# 15_LMS2_RF1_Misc.net
KiCad netlist of a schematic drawn in Altium Designer
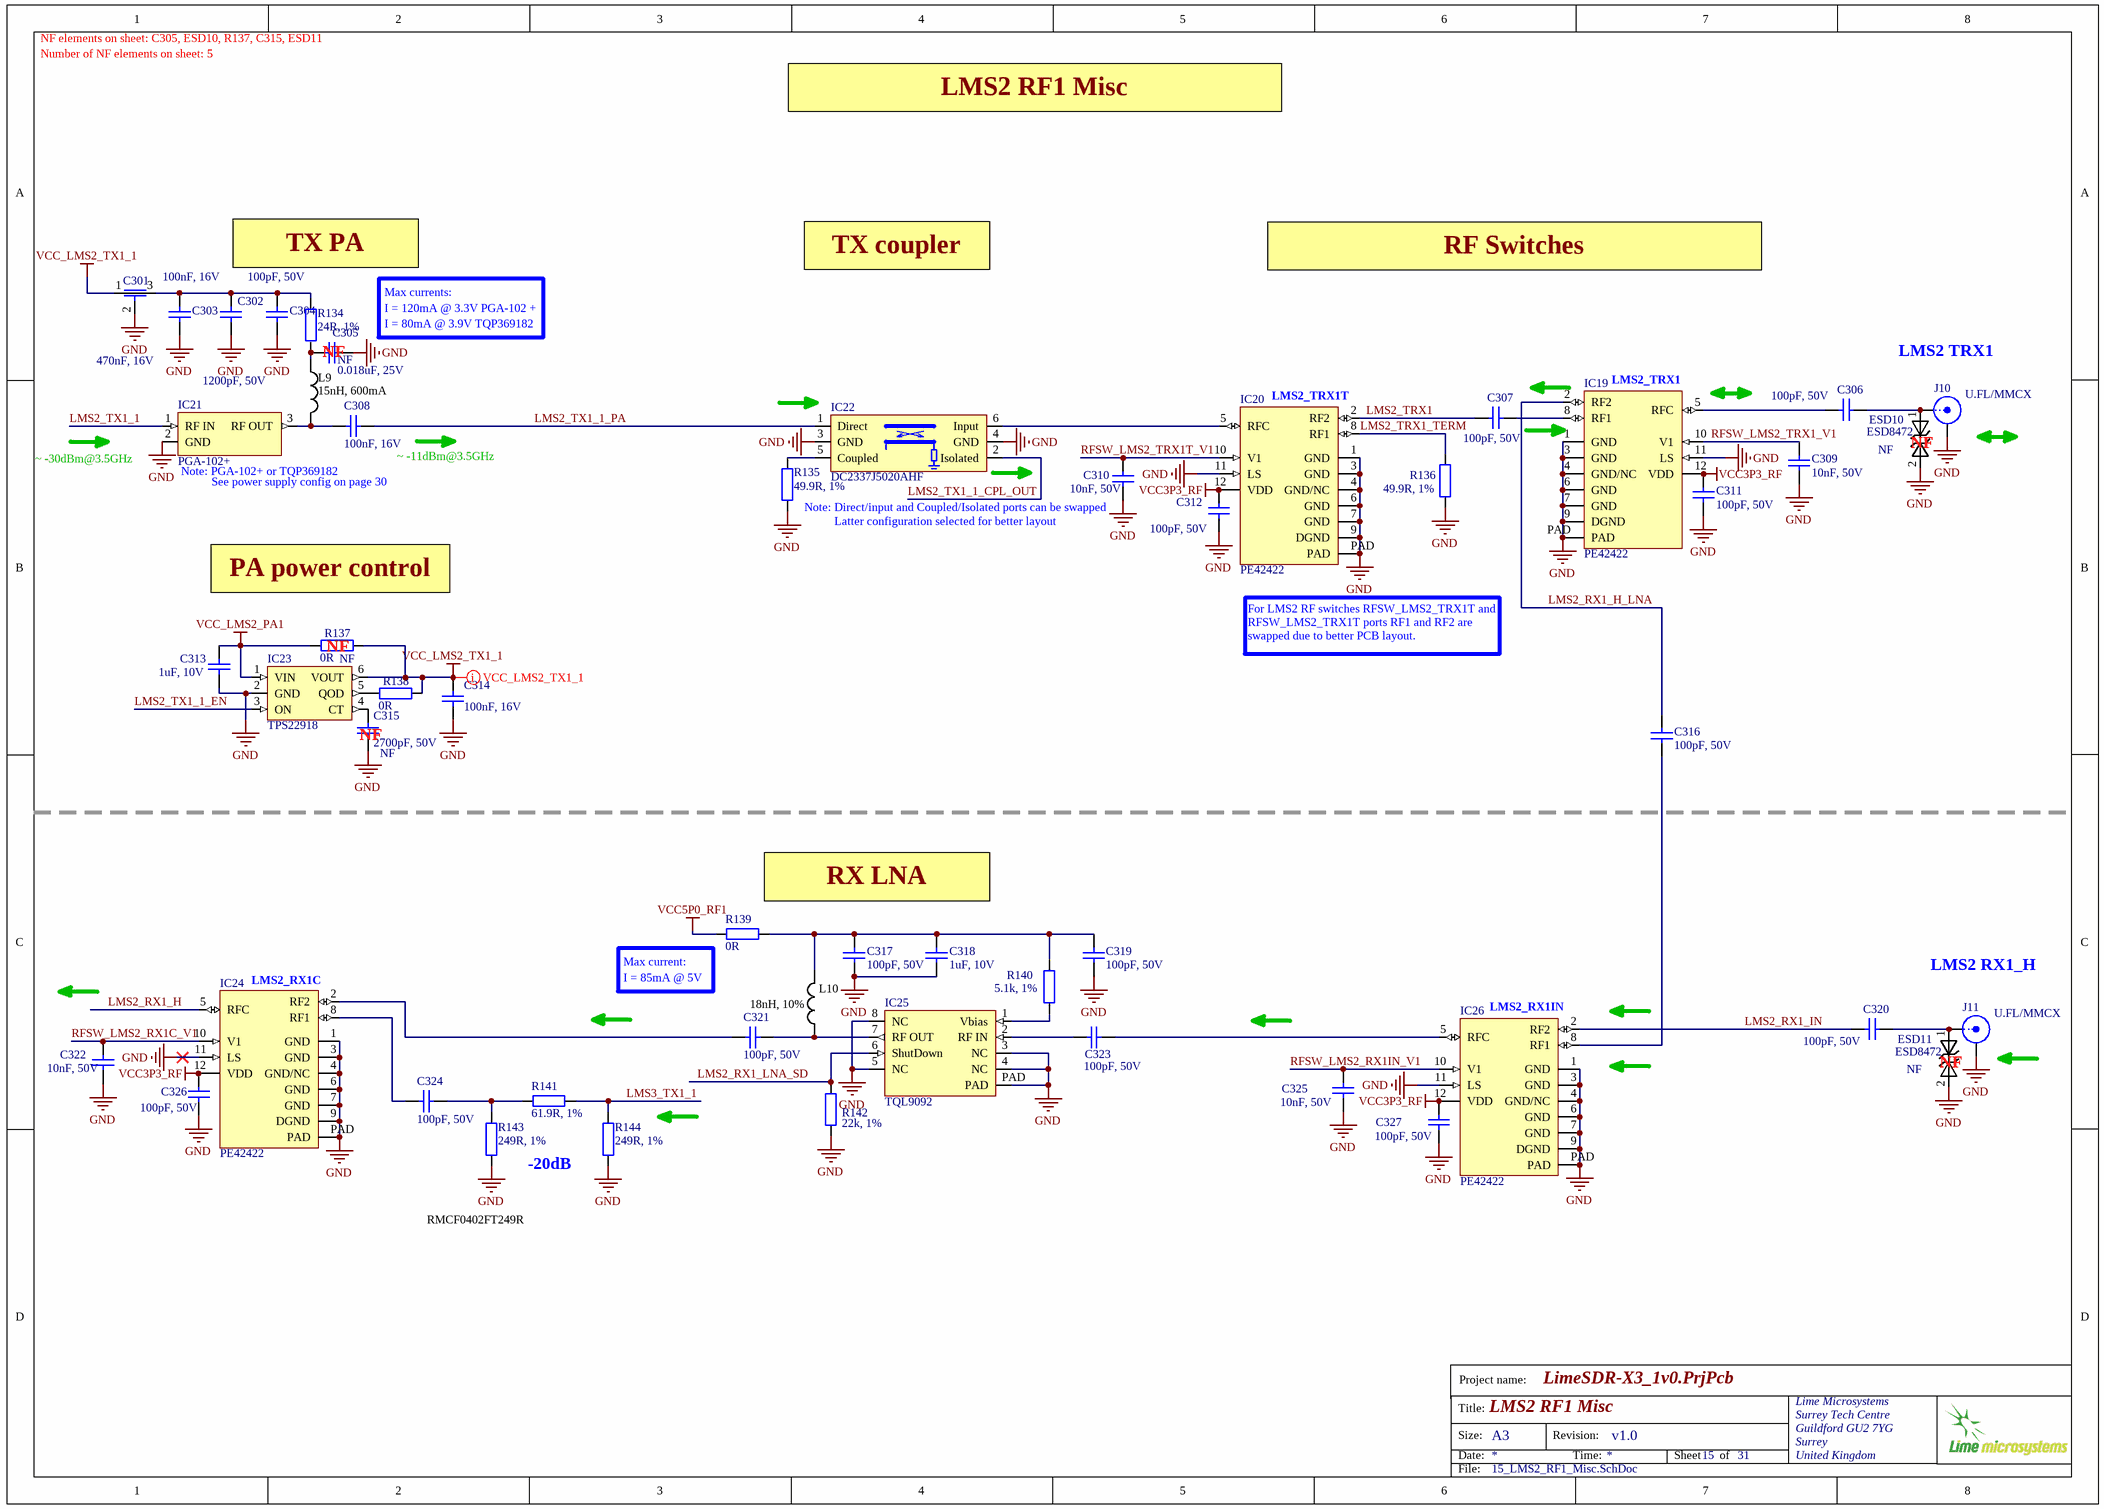
[diagram p0: 15_LMS2_RF1_Misc.SchDoc]

(export (version "E")
  (design (tool "Eeschema 10.0.6"))
  (components
    (comp (ref "C301")
      (value "470nF, 16V")
      (footprint "CAP0805_FEEDTHROUGH")
      (fields
        (field (name "MANUFACTURER") "Murata")
        (field (name "TOLERANCE") "20%")
        (field (name "VOLTAGE") "16V")
      )
      (libsource (lib "LimeMicroAltiumLib_schLib_r01") (part "Cap_feed_through"))
    )
    (comp (ref "C302")
      (value "1200pF, 50V")
      (footprint "CAP0402")
      (fields (field (name "MANUFACTURER") "Kemet") (field (name "TOLERANCE") "±5%"))
      (libsource (lib "") (part "Cap_0402_11"))
    )
    (comp (ref "C303")
      (value "100nF, 16V")
      (footprint "CAP0402")
      (fields (field (name "MANUFACTURER") "Murata Electronics") (field (name "TOLERANCE") "10 %"))
      (libsource (lib "") (part "Cap_0402_4"))
    )
    (comp (ref "C304")
      (value "100pF, 50V")
      (footprint "CAP0402")
      (fields (field (name "TOLERANCE") "±5%") (field (name "MANUFACTURER") "Yageo"))
      (libsource (lib "") (part "Cap_0402_4"))
    )
    (comp (ref "C305")
      (value "0.018uF, 25V")
      (footprint "CAP0402")
      (fields
        (field (name "ASSEMBLY INFO") "NF")
        (field (name "MANUFACTURER") "Yageo")
        (field (name "TOLERANCE") "10%")
      )
      (libsource (lib "") (part "Cap_0402_2"))
    )
    (comp (ref "C306")
      (value "100pF, 50V")
      (footprint "CAP0402")
      (fields (field (name "TOLERANCE") "±5%") (field (name "MANUFACTURER") "Yageo"))
      (libsource (lib "") (part "Cap_0402_1"))
    )
    (comp (ref "C307")
      (value "100pF, 50V")
      (footprint "CAP0402")
      (fields (field (name "TOLERANCE") "±5%") (field (name "MANUFACTURER") "Yageo"))
      (libsource (lib "") (part "Cap_0402_1"))
    )
    (comp (ref "C308")
      (value "100nF, 16V")
      (footprint "CAP0402")
      (fields (field (name "MANUFACTURER") "Murata Electronics") (field (name "TOLERANCE") "10 %"))
      (libsource (lib "") (part "Cap_0402_5"))
    )
    (comp (ref "C309")
      (value "10nF, 50V")
      (footprint "CAP0402")
      (fields
        (field (name "MANUFACTURER") "Murata Electronics North America")
        (field (name "TOLERANCE") "±10%")
      )
      (libsource (lib "") (part "Cap_0402_10"))
    )
    (comp (ref "C310")
      (value "10nF, 50V")
      (footprint "CAP0402")
      (fields
        (field (name "MANUFACTURER") "Murata Electronics North America")
        (field (name "TOLERANCE") "±10%")
      )
      (libsource (lib "") (part "Cap_0402_10"))
    )
    (comp (ref "C311")
      (value "100pF, 50V")
      (footprint "CAP0402")
      (fields (field (name "TOLERANCE") "±5%") (field (name "MANUFACTURER") "Yageo"))
      (libsource (lib "") (part "Cap_0402_6"))
    )
    (comp (ref "C312")
      (value "100pF, 50V")
      (footprint "CAP0402")
      (fields (field (name "TOLERANCE") "±5%") (field (name "MANUFACTURER") "Yageo"))
      (libsource (lib "") (part "Cap_0402_6"))
    )
    (comp (ref "C313")
      (value "1uF, 10V")
      (footprint "CAP0402")
      (fields (field (name "MANUFACTURER") "TDK"))
      (libsource (lib "LimeMicroAltiumLib_schLib") (part "Cap_0402"))
    )
    (comp (ref "C314")
      (value "100nF, 16V")
      (footprint "CAP0402")
      (fields (field (name "MANUFACTURER") "Murata Electronics") (field (name "TOLERANCE") "10 %"))
      (libsource (lib "LimeMicroAltiumLib_schLib") (part "Cap_0402"))
    )
    (comp (ref "C315")
      (value "2700pF, 50V")
      (footprint "CAP0402")
      (fields
        (field (name "ASSEMBLY INFO") "NF")
        (field (name "TOLERANCE") "±10%")
        (field (name "MANUFACTURER") "Murata Electronics North America")
      )
      (libsource (lib "") (part "Cap_0402_4"))
    )
    (comp (ref "C316")
      (value "100pF, 50V")
      (footprint "CAP0402")
      (fields (field (name "TOLERANCE") "±5%") (field (name "MANUFACTURER") "Yageo"))
      (libsource (lib "") (part "Cap_0402_1"))
    )
    (comp (ref "C317")
      (value "100pF, 50V")
      (footprint "CAP0402")
      (fields (field (name "TOLERANCE") "±5%") (field (name "MANUFACTURER") "Yageo"))
      (libsource (lib "") (part "Cap_0402_3"))
    )
    (comp (ref "C318")
      (value "1uF, 10V")
      (footprint "CAP0402")
      (fields (field (name "MANUFACTURER") "TDK"))
      (libsource (lib "") (part "Cap_0402_8"))
    )
    (comp (ref "C319")
      (value "100pF, 50V")
      (footprint "CAP0402")
      (fields (field (name "TOLERANCE") "±5%") (field (name "MANUFACTURER") "Yageo"))
      (libsource (lib "") (part "Cap_0402_3"))
    )
    (comp (ref "C320")
      (value "100pF, 50V")
      (footprint "CAP0402")
      (fields (field (name "TOLERANCE") "±5%") (field (name "MANUFACTURER") "Yageo"))
      (libsource (lib "") (part "Cap_0402_1"))
    )
    (comp (ref "C321")
      (value "100pF, 50V")
      (footprint "CAP0402")
      (fields (field (name "TOLERANCE") "±5%") (field (name "MANUFACTURER") "Yageo"))
      (libsource (lib "LimeMicroAltiumLib_schLib") (part "Cap_0402"))
    )
    (comp (ref "C322")
      (value "10nF, 50V")
      (footprint "CAP0402")
      (fields
        (field (name "MANUFACTURER") "Murata Electronics North America")
        (field (name "TOLERANCE") "±10%")
      )
      (libsource (lib "") (part "Cap_0402_12"))
    )
    (comp (ref "C323")
      (value "100pF, 50V")
      (footprint "CAP0402")
      (fields (field (name "TOLERANCE") "±5%") (field (name "MANUFACTURER") "Yageo"))
      (libsource (lib "") (part "Cap_0402_7"))
    )
    (comp (ref "C324")
      (value "100pF, 50V")
      (footprint "CAP0402")
      (fields (field (name "TOLERANCE") "±5%") (field (name "MANUFACTURER") "Yageo"))
      (libsource (lib "") (part "Cap_0402_1"))
    )
    (comp (ref "C325")
      (value "10nF, 50V")
      (footprint "CAP0402")
      (fields
        (field (name "MANUFACTURER") "Murata Electronics North America")
        (field (name "TOLERANCE") "±10%")
      )
      (libsource (lib "") (part "Cap_0402_2"))
    )
    (comp (ref "C326")
      (value "100pF, 50V")
      (footprint "CAP0402")
      (fields (field (name "TOLERANCE") "±5%") (field (name "MANUFACTURER") "Yageo"))
      (libsource (lib "") (part "Cap_0402_9"))
    )
    (comp (ref "C327")
      (value "100pF, 50V")
      (footprint "CAP0402")
      (fields (field (name "TOLERANCE") "±5%") (field (name "MANUFACTURER") "Yageo"))
      (libsource (lib "") (part "Cap_0402_5"))
    )
    (comp (ref "ESD10")
      (value "ESD8472")
      (footprint "ESD8472_X3DFN2")
      (fields (field (name "MANUFACTURER") "ON Semiconductor") (field (name "ASSEMBLY INFO") "NF"))
      (libsource (lib "") (part "ESD8472_1"))
    )
    (comp (ref "ESD11")
      (value "ESD8472")
      (footprint "ESD8472_X3DFN2")
      (fields (field (name "MANUFACTURER") "ON Semiconductor") (field (name "ASSEMBLY INFO") "NF"))
      (libsource (lib "LimeMicroAltiumLib_schLib") (part "ESD8472"))
    )
    (comp (ref "IC19")
      (value "PE42422")
      (footprint "PE42422_QFN12")
      (fields (field (name "MANUFACTURER") "Peregrine Semiconductor"))
      (libsource (lib "") (part "PE42422_2"))
    )
    (comp (ref "IC20")
      (value "PE42422")
      (footprint "PE42422_QFN12")
      (fields (field (name "MANUFACTURER") "Peregrine Semiconductor"))
      (libsource (lib "LimeMicroAltiumLib_schLib") (part "PE42422"))
    )
    (comp (ref "IC21")
      (value "PGA-102+")
      (footprint "PGA-102+_SOT89")
      (fields (field (name "MANUFACTURER") "Qorvo"))
      (libsource (lib "LimeMicroAltiumLib_schLib_r01") (part "PGA-102+_PA"))
    )
    (comp (ref "IC22")
      (value "DC2337J5020AHF")
      (footprint "DC2337J5020AHF_ANAREN_COUPLER_0805")
      (fields (field (name "MANUFACTURER") "Anaren"))
      (libsource (lib "LimeMicroAltiumLib_schLib_r02") (part "DC2337J5020AHF_coupler"))
    )
    (comp (ref "IC23")
      (value "TPS22918")
      (footprint "SOT23-6")
      (fields (field (name "MANUFACTURER") "Texas Instruments"))
      (libsource (lib "LimeMicroAltiumLib_schLib") (part "TPS22918"))
    )
    (comp (ref "IC24")
      (value "PE42422")
      (footprint "PE42422_QFN12")
      (fields (field (name "MANUFACTURER") "Peregrine Semiconductor"))
      (libsource (lib "") (part "PE42422_3"))
    )
    (comp (ref "IC25")
      (value "TQL9092")
      (footprint "TQL9092")
      (fields (field (name "MANUFACTURER") "Qorvo"))
      (libsource (lib "LimeMicroAltiumLib_schLib") (part "TQL9092"))
    )
    (comp (ref "IC26")
      (value "PE42422")
      (footprint "PE42422_QFN12")
      (fields (field (name "MANUFACTURER") "Peregrine Semiconductor"))
      (libsource (lib "") (part "PE42422_1"))
    )
    (comp (ref "J10")
      (value "U.FL/MMCX")
      (footprint "MMCX_UFL_conn_m")
      (description "CONN UMC RCPT STR 50 OHM SMD")
      (fields (field (name "MANUFACTURER") "Amphenol RF"))
      (libsource (lib "LimeMicroAltiumLib_schLib") (part "RF_IF_connector"))
    )
    (comp (ref "J11")
      (value "U.FL/MMCX")
      (footprint "MMCX_UFL_conn_m")
      (description "CONN UMC RCPT STR 50 OHM SMD")
      (fields (field (name "MANUFACTURER") "Amphenol RF"))
      (libsource (lib "LimeMicroAltiumLib_schLib") (part "RF_IF_connector"))
    )
    (comp (ref "L9")
      (value "15nH, 600mA")
      (footprint "RES0805")
      (fields (field (name "MANUFACTURER") "Bourns") (field (name "TOLERANCE") "5%"))
      (libsource (lib "LimeMicroAltiumLib_schLib") (part "Inductor_0603"))
    )
    (comp (ref "L10")
      (value "18nH, 10%")
      (footprint "RES0603")
      (fields (field (name "MANUFACTURER") "Pulse Electronics Network") (field (name "TOLERANCE") "±10%"))
      (libsource (lib "LimeMicroAltiumLib_schLib") (part "Inductor"))
    )
    (comp (ref "R134")
      (value "24R, 1%")
      (footprint "RES0402")
      (fields (field (name "MANUFACTURER") "Yageo") (field (name "TOLERANCE") "1%"))
      (libsource (lib "LimeFPGAboard_schLib") (part "Res_0402"))
    )
    (comp (ref "R135")
      (value "49.9R, 1%")
      (footprint "RES0402")
      (fields
        (field (name "TOLERANCE") "±1%")
        (field (name "MANUFACTURER") "Samsung Electro-Mechanics America, Inc.")
        (field (name "MANUFACTURER PART NUMBER") "RC1005F49R9CS")
      )
      (libsource (lib "LimeMicroAltiumLib_schLib") (part "Res_0402"))
    )
    (comp (ref "R136")
      (value "49.9R, 1%")
      (footprint "RES0402")
      (fields
        (field (name "TOLERANCE") "±1%")
        (field (name "MANUFACTURER") "Samsung Electro-Mechanics America, Inc.")
        (field (name "MANUFACTURER PART NUMBER") "RC1005F49R9CS")
      )
      (libsource (lib "LimeMicroAltiumLib_schLib") (part "Res_0402"))
    )
    (comp (ref "R137")
      (value "0R")
      (footprint "RES0402")
      (fields
        (field (name "ASSEMBLY INFO") "NF")
        (field (name "MANUFACTURER") "Yageo")
        (field (name "TOLERANCE") "Jumper")
      )
      (libsource (lib "") (part "Res_0402_1"))
    )
    (comp (ref "R138")
      (value "0R")
      (footprint "RES0402")
      (fields (field (name "MANUFACTURER") "Yageo") (field (name "TOLERANCE") "Jumper"))
      (libsource (lib "") (part "Res_0402_1"))
    )
    (comp (ref "R139")
      (value "0R")
      (footprint "RES0402")
      (fields (field (name "MANUFACTURER") "Yageo") (field (name "TOLERANCE") "Jumper"))
      (libsource (lib "LimeMicroAltiumLib_schLib") (part "Res_0402"))
    )
    (comp (ref "R140")
      (value "5.1k, 1%")
      (footprint "RES0603")
      (fields (field (name "MANUFACTURER") "Stackpole Electronics") (field (name "TOLERANCE") "1%"))
      (libsource (lib "LimeMicroAltiumLib_schLib") (part "Res_0603"))
    )
    (comp (ref "R141")
      (value "61.9R, 1%")
      (footprint "RES0402")
      (fields (field (name "MANUFACTURER") "Yageo") (field (name "TOLERANCE") "1%"))
      (libsource (lib "") (part "Res_0402_1"))
    )
    (comp (ref "R142")
      (value "22k, 1%")
      (footprint "RES0402")
      (fields (field (name "MANUFACTURER") "Yageo") (field (name "TOLERANCE") "±1%"))
      (libsource (lib "") (part "Res_0402_1"))
    )
    (comp (ref "R143")
      (value "249R, 1%")
      (footprint "RES0402")
      (fields (field (name "MANUFACTURER") "Stackpole Electronics Inc") (field (name "TOLERANCE") "±1%"))
      (libsource (lib "") (part "Res_0402_1"))
    )
    (comp (ref "R144")
      (value "249R, 1%")
      (footprint "RES0402")
      (fields (field (name "MANUFACTURER") "Stackpole Electronics Inc") (field (name "TOLERANCE") "±1%"))
      (libsource (lib "") (part "Res_0402_1"))
    )
  )
  (nets
    (net (code "1") (name "/LMS2_RX1_H") (class "Default")
      (node (ref "IC24") (pin "5") (pinfunction "RFC_5") (pintype "bidirectional"))
    )
    (net (code "2") (name "/LMS2_RX1_H_LNA") (class "Default")
      (node (ref "C316") (pin "2") (pinfunction "2_2") (pintype "passive"))
      (node (ref "IC19") (pin "2") (pinfunction "RF2_2") (pintype "bidirectional"))
    )
    (net (code "3") (name "/LMS2_RX1_IN") (class "Default")
      (node (ref "C320") (pin "1") (pinfunction "1_1") (pintype "passive"))
      (node (ref "IC26") (pin "2") (pinfunction "RF2_2") (pintype "bidirectional"))
    )
    (net (code "4") (name "/LMS2_RX1_LNA_SD") (class "Default")
      (node (ref "IC25") (pin "6") (pinfunction "ShutDown_6") (pintype "input"))
      (node (ref "R142") (pin "2") (pinfunction "2_2") (pintype "passive"))
    )
    (net (code "5") (name "/LMS2_TRX1") (class "Default")
      (node (ref "C307") (pin "1") (pinfunction "1_1") (pintype "passive"))
      (node (ref "IC20") (pin "2") (pinfunction "RF2_2") (pintype "bidirectional"))
    )
    (net (code "6") (name "/LMS2_TRX1_TERM") (class "Default")
      (node (ref "IC20") (pin "8") (pinfunction "RF1_8") (pintype "bidirectional"))
      (node (ref "R136") (pin "1") (pinfunction "1_1") (pintype "passive"))
    )
    (net (code "7") (name "/LMS2_TX1_1") (class "Default")
      (node (ref "IC21") (pin "1") (pinfunction "RF_IN_1") (pintype "input"))
    )
    (net (code "8") (name "/LMS2_TX1_1_CPL_OUT") (class "Default")
      (node (ref "IC22") (pin "2") (pinfunction "Isolated_2") (pintype "passive"))
    )
    (net (code "9") (name "/LMS2_TX1_1_EN") (class "Default")
      (node (ref "IC23") (pin "3") (pinfunction "ON_3") (pintype "input"))
    )
    (net (code "10") (name "/LMS2_TX1_1_PA") (class "Default")
      (node (ref "C308") (pin "1") (pinfunction "1_1") (pintype "passive"))
      (node (ref "IC22") (pin "1") (pinfunction "Direct_1") (pintype "passive"))
    )
    (net (code "11") (name "/LMS3_TX1_1") (class "Default")
      (node (ref "R141") (pin "2") (pinfunction "2_2") (pintype "passive"))
      (node (ref "R144") (pin "2") (pinfunction "2_2") (pintype "passive"))
    )
    (net (code "12") (name "/RFSW_LMS2_RX1C_V1") (class "Default")
      (node (ref "C322") (pin "1") (pinfunction "1_1") (pintype "passive"))
      (node (ref "IC24") (pin "10") (pinfunction "V1_10") (pintype "input"))
    )
    (net (code "13") (name "/RFSW_LMS2_RX1IN_V1") (class "Default")
      (node (ref "C325") (pin "1") (pinfunction "1_1") (pintype "passive"))
      (node (ref "IC26") (pin "10") (pinfunction "V1_10") (pintype "input"))
    )
    (net (code "14") (name "/RFSW_LMS2_TRX1T_V1") (class "Default")
      (node (ref "C310") (pin "1") (pinfunction "1_1") (pintype "passive"))
      (node (ref "IC20") (pin "10") (pinfunction "V1_10") (pintype "input"))
    )
    (net (code "15") (name "/RFSW_LMS2_TRX1_V1") (class "Default")
      (node (ref "C309") (pin "1") (pinfunction "1_1") (pintype "passive"))
      (node (ref "IC19") (pin "10") (pinfunction "V1_10") (pintype "input"))
    )
    (net (code "16") (name "GND") (class "Default")
      (node (ref "C301") (pin "2") (pinfunction "2_2") (pintype "passive"))
      (node (ref "C302") (pin "2") (pinfunction "2_2") (pintype "passive"))
      (node (ref "C303") (pin "1") (pinfunction "1_1") (pintype "passive"))
      (node (ref "C304") (pin "2") (pinfunction "2_2") (pintype "passive"))
      (node (ref "C305") (pin "2") (pinfunction "2_2") (pintype "passive"))
      (node (ref "C309") (pin "2") (pinfunction "2_2") (pintype "passive"))
      (node (ref "C310") (pin "2") (pinfunction "2_2") (pintype "passive"))
      (node (ref "C311") (pin "1") (pinfunction "1_1") (pintype "passive"))
      (node (ref "C312") (pin "1") (pinfunction "1_1") (pintype "passive"))
      (node (ref "C313") (pin "1") (pinfunction "1_1") (pintype "passive"))
      (node (ref "C314") (pin "1") (pinfunction "1_1") (pintype "passive"))
      (node (ref "C315") (pin "2") (pinfunction "2_2") (pintype "passive"))
      (node (ref "C317") (pin "2") (pinfunction "2_2") (pintype "passive"))
      (node (ref "C318") (pin "1") (pinfunction "1_1") (pintype "passive"))
      (node (ref "C319") (pin "2") (pinfunction "2_2") (pintype "passive"))
      (node (ref "C322") (pin "2") (pinfunction "2_2") (pintype "passive"))
      (node (ref "C325") (pin "2") (pinfunction "2_2") (pintype "passive"))
      (node (ref "C326") (pin "1") (pinfunction "1_1") (pintype "passive"))
      (node (ref "C327") (pin "1") (pinfunction "1_1") (pintype "passive"))
      (node (ref "ESD10") (pin "2") (pinfunction "2_2") (pintype "passive"))
      (node (ref "ESD11") (pin "2") (pinfunction "2_2") (pintype "passive"))
      (node (ref "IC19") (pin "1") (pinfunction "GND_1") (pintype "passive"))
      (node (ref "IC19") (pin "11") (pinfunction "LS_11") (pintype "input"))
      (node (ref "IC19") (pin "3") (pinfunction "GND_3") (pintype "passive"))
      (node (ref "IC19") (pin "4") (pinfunction "GND/NC_4") (pintype "passive"))
      (node (ref "IC19") (pin "6") (pinfunction "GND_6") (pintype "passive"))
      (node (ref "IC19") (pin "7") (pinfunction "GND_7") (pintype "passive"))
      (node (ref "IC19") (pin "9") (pinfunction "DGND_9") (pintype "passive"))
      (node (ref "IC19") (pin "PAD") (pinfunction "PAD_PAD") (pintype "passive"))
      (node (ref "IC20") (pin "1") (pinfunction "GND_1") (pintype "passive"))
      (node (ref "IC20") (pin "11") (pinfunction "LS_11") (pintype "input"))
      (node (ref "IC20") (pin "3") (pinfunction "GND_3") (pintype "passive"))
      (node (ref "IC20") (pin "4") (pinfunction "GND/NC_4") (pintype "passive"))
      (node (ref "IC20") (pin "6") (pinfunction "GND_6") (pintype "passive"))
      (node (ref "IC20") (pin "7") (pinfunction "GND_7") (pintype "passive"))
      (node (ref "IC20") (pin "9") (pinfunction "DGND_9") (pintype "passive"))
      (node (ref "IC20") (pin "PAD") (pinfunction "PAD_PAD") (pintype "passive"))
      (node (ref "IC21") (pin "2") (pinfunction "GND_2") (pintype "passive"))
      (node (ref "IC22") (pin "3") (pinfunction "GND_3") (pintype "passive"))
      (node (ref "IC22") (pin "4") (pinfunction "GND_4") (pintype "passive"))
      (node (ref "IC23") (pin "2") (pinfunction "GND_2") (pintype "passive"))
      (node (ref "IC24") (pin "1") (pinfunction "GND_1") (pintype "passive"))
      (node (ref "IC24") (pin "11") (pinfunction "LS_11") (pintype "input"))
      (node (ref "IC24") (pin "3") (pinfunction "GND_3") (pintype "passive"))
      (node (ref "IC24") (pin "4") (pinfunction "GND/NC_4") (pintype "passive"))
      (node (ref "IC24") (pin "6") (pinfunction "GND_6") (pintype "passive"))
      (node (ref "IC24") (pin "7") (pinfunction "GND_7") (pintype "passive"))
      (node (ref "IC24") (pin "9") (pinfunction "DGND_9") (pintype "passive"))
      (node (ref "IC24") (pin "PAD") (pinfunction "PAD_PAD") (pintype "passive"))
      (node (ref "IC25") (pin "3") (pinfunction "NC_3") (pintype "passive"))
      (node (ref "IC25") (pin "4") (pinfunction "NC_4") (pintype "passive"))
      (node (ref "IC25") (pin "5") (pinfunction "NC_5") (pintype "passive"))
      (node (ref "IC25") (pin "8") (pinfunction "NC_8") (pintype "passive"))
      (node (ref "IC25") (pin "PAD") (pinfunction "PAD_PAD") (pintype "passive"))
      (node (ref "IC26") (pin "1") (pinfunction "GND_1") (pintype "passive"))
      (node (ref "IC26") (pin "11") (pinfunction "LS_11") (pintype "input"))
      (node (ref "IC26") (pin "3") (pinfunction "GND_3") (pintype "passive"))
      (node (ref "IC26") (pin "4") (pinfunction "GND/NC_4") (pintype "passive"))
      (node (ref "IC26") (pin "6") (pinfunction "GND_6") (pintype "passive"))
      (node (ref "IC26") (pin "7") (pinfunction "GND_7") (pintype "passive"))
      (node (ref "IC26") (pin "9") (pinfunction "DGND_9") (pintype "passive"))
      (node (ref "IC26") (pin "PAD") (pinfunction "PAD_PAD") (pintype "passive"))
      (node (ref "J10") (pin "2") (pinfunction "Y_2") (pintype "passive"))
      (node (ref "J11") (pin "2") (pinfunction "Y_2") (pintype "passive"))
      (node (ref "R135") (pin "2") (pinfunction "2_2") (pintype "passive"))
      (node (ref "R136") (pin "2") (pinfunction "2_2") (pintype "passive"))
      (node (ref "R142") (pin "1") (pinfunction "1_1") (pintype "passive"))
      (node (ref "R143") (pin "1") (pinfunction "1_1") (pintype "passive"))
      (node (ref "R144") (pin "1") (pinfunction "1_1") (pintype "passive"))
    )
    (net (code "17") (name "Net-(C301-Pad3)") (class "Default")
      (node (ref "C301") (pin "3") (pinfunction "3_3") (pintype "passive"))
      (node (ref "C302") (pin "1") (pinfunction "1_1") (pintype "passive"))
      (node (ref "C303") (pin "2") (pinfunction "2_2") (pintype "passive"))
      (node (ref "C304") (pin "1") (pinfunction "1_1") (pintype "passive"))
      (node (ref "R134") (pin "1") (pinfunction "1_1") (pintype "passive"))
    )
    (net (code "18") (name "Net-(C305-Pad1)") (class "Default")
      (node (ref "C305") (pin "1") (pinfunction "1_1") (pintype "passive"))
      (node (ref "L9") (pin "1") (pinfunction "1_1") (pintype "passive"))
      (node (ref "R134") (pin "2") (pinfunction "2_2") (pintype "passive"))
    )
    (net (code "19") (name "Net-(C317-Pad1)") (class "Default")
      (node (ref "C317") (pin "1") (pinfunction "1_1") (pintype "passive"))
      (node (ref "C318") (pin "2") (pinfunction "2_2") (pintype "passive"))
      (node (ref "C319") (pin "1") (pinfunction "1_1") (pintype "passive"))
      (node (ref "L10") (pin "1") (pinfunction "1_1") (pintype "passive"))
      (node (ref "R139") (pin "2") (pinfunction "2_2") (pintype "passive"))
      (node (ref "R140") (pin "2") (pinfunction "2_2") (pintype "passive"))
    )
    (net (code "20") (name "Net-(C324-Pad1)") (class "Default")
      (node (ref "C324") (pin "1") (pinfunction "1_1") (pintype "passive"))
      (node (ref "R141") (pin "1") (pinfunction "1_1") (pintype "passive"))
      (node (ref "R143") (pin "2") (pinfunction "2_2") (pintype "passive"))
    )
    (net (code "21") (name "Net-(IC19-RF1)") (class "Default")
      (node (ref "C307") (pin "2") (pinfunction "2_2") (pintype "passive"))
      (node (ref "IC19") (pin "8") (pinfunction "RF1_8") (pintype "bidirectional"))
    )
    (net (code "22") (name "Net-(IC19-RFC)") (class "Default")
      (node (ref "C306") (pin "1") (pinfunction "1_1") (pintype "passive"))
      (node (ref "IC19") (pin "5") (pinfunction "RFC_5") (pintype "bidirectional"))
    )
    (net (code "23") (name "Net-(IC20-RFC)") (class "Default")
      (node (ref "IC20") (pin "5") (pinfunction "RFC_5") (pintype "bidirectional"))
      (node (ref "IC22") (pin "6") (pinfunction "Input_6") (pintype "passive"))
    )
    (net (code "24") (name "Net-(IC21-RF_OUT)") (class "Default")
      (node (ref "C308") (pin "2") (pinfunction "2_2") (pintype "passive"))
      (node (ref "IC21") (pin "3") (pinfunction "RF_OUT_3") (pintype "output"))
      (node (ref "L9") (pin "2") (pinfunction "2_2") (pintype "passive"))
    )
    (net (code "25") (name "Net-(IC22-Coupled)") (class "Default")
      (node (ref "IC22") (pin "5") (pinfunction "Coupled_5") (pintype "passive"))
      (node (ref "R135") (pin "1") (pinfunction "1_1") (pintype "passive"))
    )
    (net (code "26") (name "Net-(IC23-CT)") (class "Default")
      (node (ref "C315") (pin "1") (pinfunction "1_1") (pintype "passive"))
      (node (ref "IC23") (pin "4") (pinfunction "CT_4") (pintype "output"))
    )
    (net (code "27") (name "Net-(IC23-QOD)") (class "Default")
      (node (ref "IC23") (pin "5") (pinfunction "QOD_5") (pintype "output"))
      (node (ref "R138") (pin "2") (pinfunction "2_2") (pintype "passive"))
    )
    (net (code "28") (name "Net-(IC24-RF1)") (class "Default")
      (node (ref "C324") (pin "2") (pinfunction "2_2") (pintype "passive"))
      (node (ref "IC24") (pin "8") (pinfunction "RF1_8") (pintype "bidirectional"))
    )
    (net (code "29") (name "Net-(IC24-RF2)") (class "Default")
      (node (ref "C321") (pin "1") (pinfunction "1_1") (pintype "passive"))
      (node (ref "IC24") (pin "2") (pinfunction "RF2_2") (pintype "bidirectional"))
    )
    (net (code "30") (name "Net-(IC25-RF_IN)") (class "Default")
      (node (ref "C323") (pin "1") (pinfunction "1_1") (pintype "passive"))
      (node (ref "IC25") (pin "2") (pinfunction "RF_IN_2") (pintype "input"))
    )
    (net (code "31") (name "Net-(IC25-RF_OUT)") (class "Default")
      (node (ref "C321") (pin "2") (pinfunction "2_2") (pintype "passive"))
      (node (ref "IC25") (pin "7") (pinfunction "RF_OUT_7") (pintype "output"))
      (node (ref "L10") (pin "2") (pinfunction "2_2") (pintype "passive"))
    )
    (net (code "32") (name "Net-(IC25-Vbias)") (class "Default")
      (node (ref "IC25") (pin "1") (pinfunction "Vbias_1") (pintype "input"))
      (node (ref "R140") (pin "1") (pinfunction "1_1") (pintype "passive"))
    )
    (net (code "33") (name "Net-(IC26-RF1)") (class "Default")
      (node (ref "C316") (pin "1") (pinfunction "1_1") (pintype "passive"))
      (node (ref "IC26") (pin "8") (pinfunction "RF1_8") (pintype "bidirectional"))
    )
    (net (code "34") (name "Net-(IC26-RFC)") (class "Default")
      (node (ref "C323") (pin "2") (pinfunction "2_2") (pintype "passive"))
      (node (ref "IC26") (pin "5") (pinfunction "RFC_5") (pintype "bidirectional"))
    )
    (net (code "35") (name "Net-(J10-X)") (class "Default")
      (node (ref "C306") (pin "2") (pinfunction "2_2") (pintype "passive"))
      (node (ref "ESD10") (pin "1") (pinfunction "1_1") (pintype "passive"))
      (node (ref "J10") (pin "1") (pinfunction "X_1") (pintype "passive"))
    )
    (net (code "36") (name "Net-(J11-X)") (class "Default")
      (node (ref "C320") (pin "2") (pinfunction "2_2") (pintype "passive"))
      (node (ref "ESD11") (pin "1") (pinfunction "1_1") (pintype "passive"))
      (node (ref "J11") (pin "1") (pinfunction "X_1") (pintype "passive"))
    )
    (net (code "37") (name "VCC3P3_RF") (class "Default")
      (node (ref "C311") (pin "2") (pinfunction "2_2") (pintype "passive"))
      (node (ref "C312") (pin "2") (pinfunction "2_2") (pintype "passive"))
      (node (ref "C326") (pin "2") (pinfunction "2_2") (pintype "passive"))
      (node (ref "C327") (pin "2") (pinfunction "2_2") (pintype "passive"))
      (node (ref "IC19") (pin "12") (pinfunction "VDD_12") (pintype "power_in"))
      (node (ref "IC20") (pin "12") (pinfunction "VDD_12") (pintype "power_in"))
      (node (ref "IC24") (pin "12") (pinfunction "VDD_12") (pintype "power_in"))
      (node (ref "IC26") (pin "12") (pinfunction "VDD_12") (pintype "power_in"))
    )
    (net (code "38") (name "VCC5P0_RF1") (class "Default")
      (node (ref "R139") (pin "1") (pinfunction "1_1") (pintype "passive"))
    )
    (net (code "39") (name "VCC_LMS2_PA1") (class "Default")
      (node (ref "C313") (pin "2") (pinfunction "2_2") (pintype "passive"))
      (node (ref "IC23") (pin "1") (pinfunction "VIN_1") (pintype "input"))
      (node (ref "R137") (pin "2") (pinfunction "2_2") (pintype "passive"))
    )
    (net (code "40") (name "VCC_LMS2_TX1_1") (class "Default")
      (node (ref "C301") (pin "1") (pinfunction "1_1") (pintype "passive"))
      (node (ref "C314") (pin "2") (pinfunction "2_2") (pintype "passive"))
      (node (ref "IC23") (pin "6") (pinfunction "VOUT_6") (pintype "output"))
      (node (ref "R137") (pin "1") (pinfunction "1_1") (pintype "passive"))
      (node (ref "R138") (pin "1") (pinfunction "1_1") (pintype "passive"))
    )
  )
)
